# RS485.net
KiCad netlist of a schematic drawn in Altium Designer
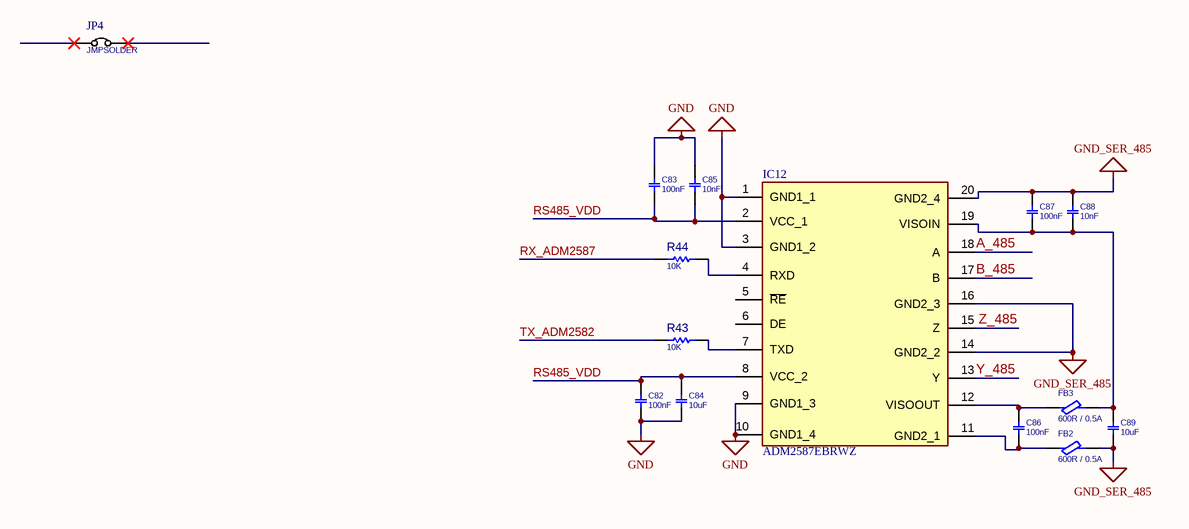
[diagram p0: RS485.SchDoc]

(export (version "E")
  (design (tool "Eeschema 10.0.6"))
  (components
    (comp (ref "C82")
      (value "100nF")
      (footprint "C0603")
      (description "CAP, MLCC")
      (fields (field (name "MANF_P#") "GRM188R61E106KA73") (field (name "MANF") "Murata"))
      (libsource (lib "mlcc_smd_passive") (part "CAP_SMD_MLCC_10u25V_0603"))
    )
    (comp (ref "C83")
      (value "100nF")
      (footprint "C0603")
      (description "CAP, MLCC")
      (fields (field (name "MANF_P#") "GRM188R61E106KA73") (field (name "MANF") "Murata"))
      (libsource (lib "mlcc_smd_passive") (part "CAP_SMD_MLCC_10u25V_0603"))
    )
    (comp (ref "C84")
      (value "10uF")
      (footprint "C0603")
      (description "CAP, MLCC")
      (fields (field (name "MANF_P#") "GRM188R61E106KA73") (field (name "MANF") "Murata"))
      (libsource (lib "mlcc_smd_passive") (part "CAP_SMD_MLCC_10u25V_0603"))
    )
    (comp (ref "C85")
      (value "10nF")
      (footprint "C0603")
      (description "CAP, MLCC")
      (fields (field (name "MANF_P#") "GRM188R61E106KA73") (field (name "MANF") "Murata"))
      (libsource (lib "mlcc_smd_passive") (part "CAP_SMD_MLCC_10u25V_0603"))
    )
    (comp (ref "C86")
      (value "100nF")
      (footprint "C0603")
      (description "CAP, MLCC")
      (fields (field (name "MANF_P#") "GRM188R61E106KA73") (field (name "MANF") "Murata"))
      (libsource (lib "mlcc_smd_passive") (part "CAP_SMD_MLCC_10u25V_0603"))
    )
    (comp (ref "C87")
      (value "100nF")
      (footprint "C0603")
      (description "CAP, MLCC")
      (fields (field (name "MANF_P#") "GRM188R61E106KA73") (field (name "MANF") "Murata"))
      (libsource (lib "mlcc_smd_passive") (part "CAP_SMD_MLCC_10u25V_0603"))
    )
    (comp (ref "C88")
      (value "10nF")
      (footprint "C0603")
      (description "CAP, MLCC")
      (fields (field (name "MANF_P#") "GRM188R61E106KA73") (field (name "MANF") "Murata"))
      (libsource (lib "mlcc_smd_passive") (part "CAP_SMD_MLCC_10u25V_0603"))
    )
    (comp (ref "C89")
      (value "10uF")
      (footprint "C0603")
      (description "CAP, MLCC")
      (fields (field (name "MANF_P#") "GRM188R61E106KA73") (field (name "MANF") "Murata"))
      (libsource (lib "mlcc_smd_passive") (part "CAP_SMD_MLCC_10u25V_0603"))
    )
    (comp (ref "FB2")
      (value "600R / 0.5A")
      (footprint "L0603")
      (description "FERRITE_Bead, 0603, 0.8A, 300mOhm, 1000@100MHz")
      (fields (field (name "MANF") "TDK") (field (name "MANF_P#") "MPZ1608S102ATA00"))
      (libsource (lib "emi_filter") (part "FBEAD_SMD_MPZ1608S102"))
    )
    (comp (ref "FB3")
      (value "600R / 0.5A")
      (footprint "L0603")
      (description "FERRITE_Bead, 0603, 0.8A, 300mOhm, 1000@100MHz")
      (fields (field (name "MANF") "TDK") (field (name "MANF_P#") "MPZ1608S102ATA00"))
      (libsource (lib "emi_filter") (part "FBEAD_SMD_MPZ1608S102"))
    )
    (comp (ref "IC12")
      (value "ADM2587EBRWZ")
      (footprint "SamacSys:SOIC127P1032X265-20N")
      (description "Integrated Circuit")
      (fields (field (name "MOUSER PART NUMBER") "584-ADM2587EBRWZ"))
      (libsource (lib "SamacSys") (part "ADM2587EBRWZ"))
    )
    (comp (ref "JP4")
      (value "JMPSOLDER")
      (footprint "JP_40X50")
      (description "JUMPER, HEADER 2PIN")
      (fields (field (name "MANF") "MANF") (field (name "MANF_P#") "MANF_P#"))
      (libsource (lib "test-tp_jumper") (part "JUMPER_SOLDER"))
    )
    (comp (ref "R43")
      (value "10K")
      (footprint "R0805")
      (description "RESISTOR, SMD")
      (libsource (lib "passive_smd") (part "RES_SMD_0805"))
    )
    (comp (ref "R44")
      (value "10K")
      (footprint "R0805")
      (description "RESISTOR, SMD")
      (libsource (lib "passive_smd") (part "RES_SMD_0805"))
    )
  )
  (nets
    (net (code "1") (name "/A_485") (class "Default")
      (node (ref "IC12") (pin "18") (pinfunction "A_18") (pintype "passive"))
    )
    (net (code "2") (name "/B_485") (class "Default")
      (node (ref "IC12") (pin "17") (pinfunction "B_17") (pintype "passive"))
    )
    (net (code "3") (name "/RS485_VDD") (class "Default")
      (node (ref "C82") (pin "2") (pinfunction "2_2") (pintype "passive"))
      (node (ref "C83") (pin "1") (pinfunction "1_1") (pintype "passive"))
      (node (ref "C84") (pin "1") (pinfunction "1_1") (pintype "passive"))
      (node (ref "C85") (pin "2") (pinfunction "2_2") (pintype "passive"))
      (node (ref "IC12") (pin "2") (pinfunction "VCC_1_2") (pintype "passive"))
      (node (ref "IC12") (pin "8") (pinfunction "VCC_2_8") (pintype "passive"))
    )
    (net (code "4") (name "/RX_ADM2587") (class "Default")
      (node (ref "R44") (pin "1") (pinfunction "1_1") (pintype "passive"))
    )
    (net (code "5") (name "/TX_ADM2582") (class "Default")
      (node (ref "R43") (pin "1") (pinfunction "1_1") (pintype "passive"))
    )
    (net (code "6") (name "/Y_485") (class "Default")
      (node (ref "IC12") (pin "13") (pinfunction "Y_13") (pintype "passive"))
    )
    (net (code "7") (name "/Z_485") (class "Default")
      (node (ref "IC12") (pin "15") (pinfunction "Z_15") (pintype "passive"))
    )
    (net (code "8") (name "GND") (class "Default")
      (node (ref "C82") (pin "1") (pinfunction "1_1") (pintype "passive"))
      (node (ref "C83") (pin "2") (pinfunction "2_2") (pintype "passive"))
      (node (ref "C84") (pin "2") (pinfunction "2_2") (pintype "passive"))
      (node (ref "C85") (pin "1") (pinfunction "1_1") (pintype "passive"))
      (node (ref "IC12") (pin "1") (pinfunction "GND1_1_1") (pintype "passive"))
      (node (ref "IC12") (pin "10") (pinfunction "GND1_4_10") (pintype "passive"))
      (node (ref "IC12") (pin "3") (pinfunction "GND1_2_3") (pintype "passive"))
      (node (ref "IC12") (pin "9") (pinfunction "GND1_3_9") (pintype "passive"))
    )
    (net (code "9") (name "GND_SER_485") (class "Default")
      (node (ref "C87") (pin "2") (pinfunction "2_2") (pintype "passive"))
      (node (ref "C88") (pin "1") (pinfunction "1_1") (pintype "passive"))
      (node (ref "C89") (pin "1") (pinfunction "1_1") (pintype "passive"))
      (node (ref "FB2") (pin "2") (pinfunction "2_2") (pintype "passive"))
      (node (ref "IC12") (pin "14") (pinfunction "GND2_2_14") (pintype "passive"))
      (node (ref "IC12") (pin "16") (pinfunction "GND2_3_16") (pintype "passive"))
      (node (ref "IC12") (pin "20") (pinfunction "GND2_4_20") (pintype "passive"))
    )
    (net (code "10") (name "Net-(IC12-GND2_1)") (class "Default")
      (node (ref "C86") (pin "1") (pinfunction "1_1") (pintype "passive"))
      (node (ref "FB2") (pin "1") (pinfunction "1_1") (pintype "passive"))
      (node (ref "IC12") (pin "11") (pinfunction "GND2_1_11") (pintype "passive"))
    )
    (net (code "11") (name "Net-(IC12-RXD)") (class "Default")
      (node (ref "IC12") (pin "4") (pinfunction "RXD_4") (pintype "passive"))
      (node (ref "R44") (pin "2") (pinfunction "2_2") (pintype "passive"))
    )
    (net (code "12") (name "Net-(IC12-TXD)") (class "Default")
      (node (ref "IC12") (pin "7") (pinfunction "TXD_7") (pintype "passive"))
      (node (ref "R43") (pin "2") (pinfunction "2_2") (pintype "passive"))
    )
    (net (code "13") (name "Net-(IC12-VISOIN)") (class "Default")
      (node (ref "C87") (pin "1") (pinfunction "1_1") (pintype "passive"))
      (node (ref "C88") (pin "2") (pinfunction "2_2") (pintype "passive"))
      (node (ref "C89") (pin "2") (pinfunction "2_2") (pintype "passive"))
      (node (ref "FB3") (pin "2") (pinfunction "2_2") (pintype "passive"))
      (node (ref "IC12") (pin "19") (pinfunction "VISOIN_19") (pintype "passive"))
    )
    (net (code "14") (name "Net-(IC12-VISOOUT)") (class "Default")
      (node (ref "C86") (pin "2") (pinfunction "2_2") (pintype "passive"))
      (node (ref "FB3") (pin "1") (pinfunction "1_1") (pintype "passive"))
      (node (ref "IC12") (pin "12") (pinfunction "VISOOUT_12") (pintype "passive"))
    )
    (net (code "15") (name "unconnected-(IC12-DE-Pad6)") (class "Default")
      (node (ref "IC12") (pin "6") (pinfunction "DE_6") (pintype "passive"))
    )
    (net (code "16") (name "unconnected-(IC12-~{RE}-Pad5)") (class "Default")
      (node (ref "IC12") (pin "5") (pinfunction "~{RE}_5") (pintype "passive"))
    )
    (net (code "17") (name "unconnected-(JP4-Pad1)") (class "Default")
      (node (ref "JP4") (pin "1") (pinfunction "1_1") (pintype "passive+no_connect"))
    )
    (net (code "18") (name "unconnected-(JP4-Pad2)") (class "Default")
      (node (ref "JP4") (pin "2") (pinfunction "2_2") (pintype "passive+no_connect"))
    )
  )
)
